# LED_Project.net
KiCad netlist of a schematic drawn in EAGLE
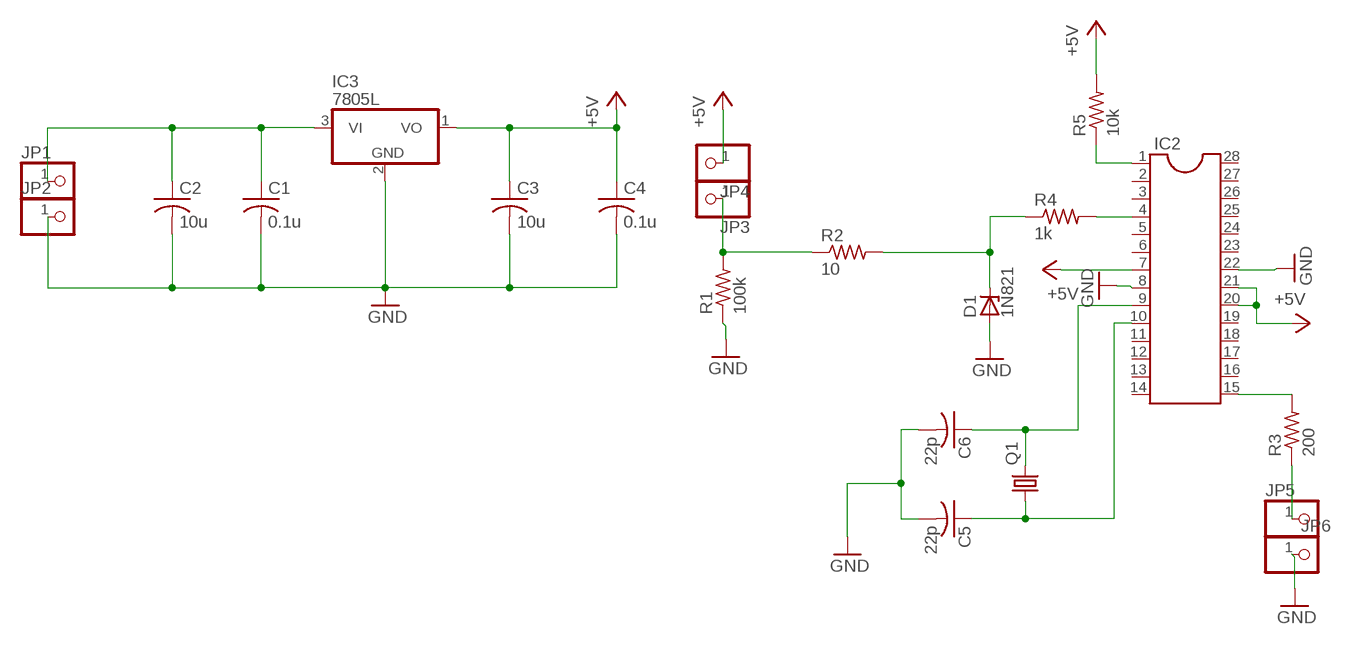
[diagram p0: schematic, sheet 1]

(export (version "E")
  (design (tool "Eeschema 10.0.6"))
  (components
    (comp (ref "C1")
      (value "0.1u")
      (footprint "eagle-import:C0805K")
      (libsource (lib "eagle-import") (part "C-USC0805K"))
    )
    (comp (ref "C2")
      (value "10u")
      (footprint "eagle-import:C0805K")
      (libsource (lib "eagle-import") (part "C-USC0805K"))
    )
    (comp (ref "C3")
      (value "10u")
      (footprint "eagle-import:C0805K")
      (libsource (lib "eagle-import") (part "C-USC0805K"))
    )
    (comp (ref "C4")
      (value "0.1u")
      (footprint "eagle-import:C0805K")
      (libsource (lib "eagle-import") (part "C-USC0805K"))
    )
    (comp (ref "C5")
      (value "22p")
      (footprint "eagle-import:C0805K")
      (libsource (lib "eagle-import") (part "C-USC0805K"))
    )
    (comp (ref "C6")
      (value "22p")
      (footprint "eagle-import:C0805K")
      (libsource (lib "eagle-import") (part "C-USC0805K"))
    )
    (comp (ref "D1")
      (value "1N821")
      (footprint "eagle-import:DO35Z10")
      (libsource (lib "eagle-import") (part "1N821"))
    )
    (comp (ref "IC2")
      (value "DIL28-3")
      (footprint "eagle-import:DIL28-3")
      (libsource (lib "eagle-import") (part "DIL28-3"))
    )
    (comp (ref "IC3")
      (value "7805L")
      (footprint "eagle-import:TO92")
      (libsource (lib "eagle-import") (part "78L05"))
    )
    (comp (ref "JP1")
      (value "PINHD-1X1")
      (footprint "eagle-import:1X01")
      (libsource (lib "eagle-import") (part "PINHD-1X1"))
    )
    (comp (ref "JP2")
      (value "PINHD-1X1")
      (footprint "eagle-import:1X01")
      (libsource (lib "eagle-import") (part "PINHD-1X1"))
    )
    (comp (ref "JP3")
      (value "PINHD-1X1")
      (footprint "eagle-import:1X01")
      (libsource (lib "eagle-import") (part "PINHD-1X1"))
    )
    (comp (ref "JP4")
      (value "PINHD-1X1")
      (footprint "eagle-import:1X01")
      (libsource (lib "eagle-import") (part "PINHD-1X1"))
    )
    (comp (ref "JP5")
      (value "PINHD-1X1")
      (footprint "eagle-import:1X01")
      (libsource (lib "eagle-import") (part "PINHD-1X1"))
    )
    (comp (ref "JP6")
      (value "PINHD-1X1")
      (footprint "eagle-import:1X01")
      (libsource (lib "eagle-import") (part "PINHD-1X1"))
    )
    (comp (ref "Q1")
      (value "CRYSTALHC49S")
      (footprint "eagle-import:HC49_S")
      (libsource (lib "eagle-import") (part "CRYSTALHC49S"))
    )
    (comp (ref "R1")
      (value "100k")
      (footprint "eagle-import:R0805")
      (libsource (lib "eagle-import") (part "R-US_R0805"))
    )
    (comp (ref "R2")
      (value "10")
      (footprint "eagle-import:R0805")
      (libsource (lib "eagle-import") (part "R-US_R0805"))
    )
    (comp (ref "R3")
      (value "200")
      (footprint "eagle-import:R0805")
      (libsource (lib "eagle-import") (part "R-US_R0805"))
    )
    (comp (ref "R4")
      (value "1k")
      (footprint "eagle-import:R0805")
      (libsource (lib "eagle-import") (part "R-US_R0805"))
    )
    (comp (ref "R5")
      (value "10k")
      (footprint "eagle-import:R0805")
      (libsource (lib "eagle-import") (part "R-US_R0805"))
    )
  )
  (nets
    (net (code "1") (name "+5V") (class "Default")
      (node (ref "C3") (pin "1") (pinfunction "1_1") (pintype "passive"))
      (node (ref "C4") (pin "1") (pinfunction "1_1") (pintype "passive"))
      (node (ref "IC2") (pin "20") (pinfunction "20_20") (pintype "passive"))
      (node (ref "IC2") (pin "21") (pinfunction "21_21") (pintype "passive"))
      (node (ref "IC2") (pin "7") (pinfunction "7_7") (pintype "passive"))
      (node (ref "IC3") (pin "1") (pinfunction "VO_1") (pintype "passive"))
      (node (ref "JP4") (pin "1") (pinfunction "1_1") (pintype "passive"))
      (node (ref "R5") (pin "2") (pinfunction "2_2") (pintype "passive"))
    )
    (net (code "2") (name "GND") (class "Default")
      (node (ref "C1") (pin "2") (pinfunction "2_2") (pintype "passive"))
      (node (ref "C2") (pin "2") (pinfunction "2_2") (pintype "passive"))
      (node (ref "C3") (pin "2") (pinfunction "2_2") (pintype "passive"))
      (node (ref "C4") (pin "2") (pinfunction "2_2") (pintype "passive"))
      (node (ref "C5") (pin "2") (pinfunction "2_2") (pintype "passive"))
      (node (ref "C6") (pin "2") (pinfunction "2_2") (pintype "passive"))
      (node (ref "D1") (pin "A") (pinfunction "A_A") (pintype "passive"))
      (node (ref "IC2") (pin "22") (pinfunction "22_22") (pintype "passive"))
      (node (ref "IC2") (pin "8") (pinfunction "8_8") (pintype "passive"))
      (node (ref "IC3") (pin "2") (pinfunction "GND_2") (pintype "passive"))
      (node (ref "JP2") (pin "1") (pinfunction "1_1") (pintype "passive"))
      (node (ref "JP6") (pin "1") (pinfunction "1_1") (pintype "passive"))
      (node (ref "R1") (pin "1") (pinfunction "1_1") (pintype "passive"))
    )
    (net (code "3") (name "Net-(C5-Pad1)") (class "Default")
      (node (ref "C5") (pin "1") (pinfunction "1_1") (pintype "passive"))
      (node (ref "IC2") (pin "10") (pinfunction "10_10") (pintype "passive"))
      (node (ref "Q1") (pin "1") (pinfunction "1_1") (pintype "passive"))
    )
    (net (code "4") (name "Net-(C6-Pad1)") (class "Default")
      (node (ref "C6") (pin "1") (pinfunction "1_1") (pintype "passive"))
      (node (ref "IC2") (pin "9") (pinfunction "9_9") (pintype "passive"))
      (node (ref "Q1") (pin "2") (pinfunction "2_2") (pintype "passive"))
    )
    (net (code "5") (name "Net-(D1-PadC)") (class "Default")
      (node (ref "D1") (pin "C") (pinfunction "C_C") (pintype "passive"))
      (node (ref "R2") (pin "2") (pinfunction "2_2") (pintype "passive"))
      (node (ref "R4") (pin "1") (pinfunction "1_1") (pintype "passive"))
    )
    (net (code "6") (name "Net-(IC2-Pad1)") (class "Default")
      (node (ref "IC2") (pin "1") (pinfunction "1_1") (pintype "passive"))
      (node (ref "R5") (pin "1") (pinfunction "1_1") (pintype "passive"))
    )
    (net (code "7") (name "Net-(IC2-Pad4)") (class "Default")
      (node (ref "IC2") (pin "4") (pinfunction "4_4") (pintype "passive"))
      (node (ref "R4") (pin "2") (pinfunction "2_2") (pintype "passive"))
    )
    (net (code "8") (name "Net-(IC2-Pad15)") (class "Default")
      (node (ref "IC2") (pin "15") (pinfunction "15_15") (pintype "passive"))
      (node (ref "R3") (pin "2") (pinfunction "2_2") (pintype "passive"))
    )
    (net (code "9") (name "Net-(IC3-VI)") (class "Default")
      (node (ref "C1") (pin "1") (pinfunction "1_1") (pintype "passive"))
      (node (ref "C2") (pin "1") (pinfunction "1_1") (pintype "passive"))
      (node (ref "IC3") (pin "3") (pinfunction "VI_3") (pintype "input"))
      (node (ref "JP1") (pin "1") (pinfunction "1_1") (pintype "passive"))
    )
    (net (code "10") (name "Net-(JP3-Pad1)") (class "Default")
      (node (ref "JP3") (pin "1") (pinfunction "1_1") (pintype "passive"))
      (node (ref "R1") (pin "2") (pinfunction "2_2") (pintype "passive"))
      (node (ref "R2") (pin "1") (pinfunction "1_1") (pintype "passive"))
    )
    (net (code "11") (name "Net-(JP5-Pad1)") (class "Default")
      (node (ref "JP5") (pin "1") (pinfunction "1_1") (pintype "passive"))
      (node (ref "R3") (pin "1") (pinfunction "1_1") (pintype "passive"))
    )
    (net (code "12") (name "unconnected-(IC2-Pad2)") (class "Default")
      (node (ref "IC2") (pin "2") (pinfunction "2_2") (pintype "passive"))
    )
    (net (code "13") (name "unconnected-(IC2-Pad3)") (class "Default")
      (node (ref "IC2") (pin "3") (pinfunction "3_3") (pintype "passive"))
    )
    (net (code "14") (name "unconnected-(IC2-Pad5)") (class "Default")
      (node (ref "IC2") (pin "5") (pinfunction "5_5") (pintype "passive"))
    )
    (net (code "15") (name "unconnected-(IC2-Pad6)") (class "Default")
      (node (ref "IC2") (pin "6") (pinfunction "6_6") (pintype "passive"))
    )
    (net (code "16") (name "unconnected-(IC2-Pad11)") (class "Default")
      (node (ref "IC2") (pin "11") (pinfunction "11_11") (pintype "passive"))
    )
    (net (code "17") (name "unconnected-(IC2-Pad12)") (class "Default")
      (node (ref "IC2") (pin "12") (pinfunction "12_12") (pintype "passive"))
    )
    (net (code "18") (name "unconnected-(IC2-Pad13)") (class "Default")
      (node (ref "IC2") (pin "13") (pinfunction "13_13") (pintype "passive"))
    )
    (net (code "19") (name "unconnected-(IC2-Pad14)") (class "Default")
      (node (ref "IC2") (pin "14") (pinfunction "14_14") (pintype "passive"))
    )
    (net (code "20") (name "unconnected-(IC2-Pad16)") (class "Default")
      (node (ref "IC2") (pin "16") (pinfunction "16_16") (pintype "passive"))
    )
    (net (code "21") (name "unconnected-(IC2-Pad17)") (class "Default")
      (node (ref "IC2") (pin "17") (pinfunction "17_17") (pintype "passive"))
    )
    (net (code "22") (name "unconnected-(IC2-Pad18)") (class "Default")
      (node (ref "IC2") (pin "18") (pinfunction "18_18") (pintype "passive"))
    )
    (net (code "23") (name "unconnected-(IC2-Pad19)") (class "Default")
      (node (ref "IC2") (pin "19") (pinfunction "19_19") (pintype "passive"))
    )
    (net (code "24") (name "unconnected-(IC2-Pad23)") (class "Default")
      (node (ref "IC2") (pin "23") (pinfunction "23_23") (pintype "passive"))
    )
    (net (code "25") (name "unconnected-(IC2-Pad24)") (class "Default")
      (node (ref "IC2") (pin "24") (pinfunction "24_24") (pintype "passive"))
    )
    (net (code "26") (name "unconnected-(IC2-Pad25)") (class "Default")
      (node (ref "IC2") (pin "25") (pinfunction "25_25") (pintype "passive"))
    )
    (net (code "27") (name "unconnected-(IC2-Pad26)") (class "Default")
      (node (ref "IC2") (pin "26") (pinfunction "26_26") (pintype "passive"))
    )
    (net (code "28") (name "unconnected-(IC2-Pad27)") (class "Default")
      (node (ref "IC2") (pin "27") (pinfunction "27_27") (pintype "passive"))
    )
    (net (code "29") (name "unconnected-(IC2-Pad28)") (class "Default")
      (node (ref "IC2") (pin "28") (pinfunction "28_28") (pintype "passive"))
    )
  )
)
